# ADF4356.net
KiCad netlist of a schematic drawn in Altium Designer
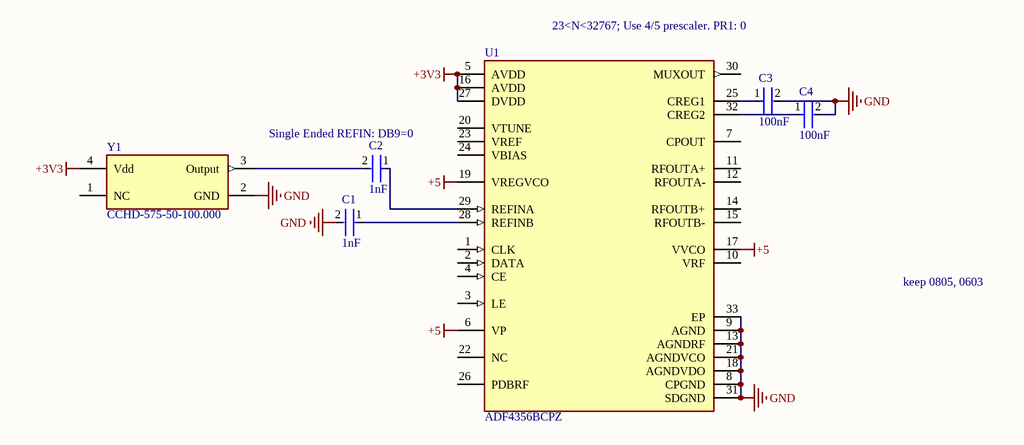
[diagram p0: ADF4356.SchDoc]

(export (version "E")
  (design (tool "Eeschema 10.0.6"))
  (components
    (comp (ref "C1")
      (value "1nF")
      (footprint "FP-C0603C-CF-MFG")
      (description "C0603 1,000 pF X7R 30ppm/°C 20.00% 50 V")
      (fields
        (field (name "MANUFACTURER PART NUMBER") "C0603C102M5RAC7411")
        (field (name "OCTOPART") "https://octopart.com/c0603c102m5rac7411-kemet-3864814")
      )
      (libsource (lib "Altium Content Vault") (part "b4654b650e69147ec39a6b967a45e02"))
    )
    (comp (ref "C2")
      (value "1nF")
      (footprint "FP-C0603C-CF-MFG")
      (description "C0603 1,000 pF X7R 30ppm/°C 20.00% 50 V")
      (fields
        (field (name "MANUFACTURER PART NUMBER") "C0603C102M5RAC7411")
        (field (name "OCTOPART") "https://octopart.com/c0603c102m5rac7411-kemet-3864814")
      )
      (libsource (lib "Altium Content Vault") (part "b4654b650e69147ec39a6b967a45e02"))
    )
    (comp (ref "C3")
      (value "100nF")
      (footprint "FP-CL21-IPC_C")
      (description "CL21 Series 0805 100nF 50V ±10% Tolerance X7R Multilayer Ceramic Chip Capacitor")
      (fields (field (name "TOLERANCE") "10%"))
      (libsource (lib "Altium Content Vault") (part "b4654b650e69147ec39a6b967a45e02"))
    )
    (comp (ref "C4")
      (value "100nF")
      (footprint "FP-CL21-IPC_C")
      (description "CL21 Series 0805 100nF 50V ±10% Tolerance X7R Multilayer Ceramic Chip Capacitor")
      (fields (field (name "TOLERANCE") "10%"))
      (libsource (lib "Altium Content Vault") (part "b4654b650e69147ec39a6b967a45e02"))
    )
    (comp (ref "U1")
      (value "ADF4356BCPZ")
      (footprint "FP-CP-32-12-IPC_B")
      (description "IC SYNTH PLL VCO 6.8GHZ 32LFCSP")
      (libsource (lib "Altium Content Vault") (part "cdbcdcc730339eae005488d77bf65b3"))
    )
    (comp (ref "Y1")
      (value "CCHD-575-50-100.000")
      (footprint "FP-CCHD-575-50-100_000-MFG")
      (description "XTAL OSC XO 100.0000MHZ HCMOS")
      (libsource (lib "Altium Content Vault") (part "8634ddfb76517a8b2207d3d7830fd32"))
    )
  )
  (nets
    (net (code "1") (name "+3V3") (class "Default")
      (node (ref "U1") (pin "16") (pinfunction "AVDD_16") (pintype "power_in"))
      (node (ref "U1") (pin "27") (pinfunction "DVDD_27") (pintype "power_in"))
      (node (ref "U1") (pin "5") (pinfunction "AVDD_5") (pintype "power_in"))
      (node (ref "Y1") (pin "4") (pinfunction "Vdd_4") (pintype "power_in"))
    )
    (net (code "2") (name "+5") (class "Default")
      (node (ref "U1") (pin "17") (pinfunction "VVCO_17") (pintype "power_in"))
      (node (ref "U1") (pin "19") (pinfunction "VREGVCO_19") (pintype "power_in"))
      (node (ref "U1") (pin "6") (pinfunction "VP_6") (pintype "passive"))
    )
    (net (code "3") (name "GND") (class "Default")
      (node (ref "C1") (pin "2") (pinfunction "2_2") (pintype "passive"))
      (node (ref "C3") (pin "2") (pinfunction "2_2") (pintype "passive"))
      (node (ref "C4") (pin "2") (pinfunction "2_2") (pintype "passive"))
      (node (ref "U1") (pin "13") (pinfunction "AGNDRF_13") (pintype "power_in"))
      (node (ref "U1") (pin "18") (pinfunction "AGNDVDO_18") (pintype "power_in"))
      (node (ref "U1") (pin "21") (pinfunction "AGNDVCO_21") (pintype "power_in"))
      (node (ref "U1") (pin "31") (pinfunction "SDGND_31") (pintype "power_in"))
      (node (ref "U1") (pin "33") (pinfunction "EP_33") (pintype "passive"))
      (node (ref "U1") (pin "8") (pinfunction "CPGND_8") (pintype "power_in"))
      (node (ref "U1") (pin "9") (pinfunction "AGND_9") (pintype "power_in"))
      (node (ref "Y1") (pin "2") (pinfunction "GND_2") (pintype "power_in"))
    )
    (net (code "4") (name "Net-(U1-CREG1)") (class "Default")
      (node (ref "C3") (pin "1") (pinfunction "1_1") (pintype "passive"))
      (node (ref "U1") (pin "25") (pinfunction "CREG1_25") (pintype "passive"))
    )
    (net (code "5") (name "Net-(U1-CREG2)") (class "Default")
      (node (ref "C4") (pin "1") (pinfunction "1_1") (pintype "passive"))
      (node (ref "U1") (pin "32") (pinfunction "CREG2_32") (pintype "passive"))
    )
    (net (code "6") (name "Net-(U1-REFINA)") (class "Default")
      (node (ref "C2") (pin "1") (pinfunction "1_1") (pintype "passive"))
      (node (ref "U1") (pin "29") (pinfunction "REFINA_29") (pintype "input"))
    )
    (net (code "7") (name "Net-(U1-REFINB)") (class "Default")
      (node (ref "C1") (pin "1") (pinfunction "1_1") (pintype "passive"))
      (node (ref "U1") (pin "28") (pinfunction "REFINB_28") (pintype "input"))
    )
    (net (code "8") (name "Net-(Y1-Output)") (class "Default")
      (node (ref "C2") (pin "2") (pinfunction "2_2") (pintype "passive"))
      (node (ref "Y1") (pin "3") (pinfunction "Output_3") (pintype "output"))
    )
    (net (code "9") (name "unconnected-(U1-CE-Pad4)") (class "Default")
      (node (ref "U1") (pin "4") (pinfunction "CE_4") (pintype "input"))
    )
    (net (code "10") (name "unconnected-(U1-CLK-Pad1)") (class "Default")
      (node (ref "U1") (pin "1") (pinfunction "CLK_1") (pintype "input"))
    )
    (net (code "11") (name "unconnected-(U1-CPOUT-Pad7)") (class "Default")
      (node (ref "U1") (pin "7") (pinfunction "CPOUT_7") (pintype "passive"))
    )
    (net (code "12") (name "unconnected-(U1-DATA-Pad2)") (class "Default")
      (node (ref "U1") (pin "2") (pinfunction "DATA_2") (pintype "input"))
    )
    (net (code "13") (name "unconnected-(U1-LE-Pad3)") (class "Default")
      (node (ref "U1") (pin "3") (pinfunction "LE_3") (pintype "input"))
    )
    (net (code "14") (name "unconnected-(U1-MUXOUT-Pad30)") (class "Default")
      (node (ref "U1") (pin "30") (pinfunction "MUXOUT_30") (pintype "output"))
    )
    (net (code "15") (name "unconnected-(U1-NC-Pad22)") (class "Default")
      (node (ref "U1") (pin "22") (pinfunction "NC_22") (pintype "passive"))
    )
    (net (code "16") (name "unconnected-(U1-PDBRF-Pad26)") (class "Default")
      (node (ref "U1") (pin "26") (pinfunction "PDBRF_26") (pintype "passive"))
    )
    (net (code "17") (name "unconnected-(U1-RFOUTA+-Pad11)") (class "Default")
      (node (ref "U1") (pin "11") (pinfunction "RFOUTA+_11") (pintype "passive"))
    )
    (net (code "18") (name "unconnected-(U1-RFOUTA--Pad12)") (class "Default")
      (node (ref "U1") (pin "12") (pinfunction "RFOUTA-_12") (pintype "passive"))
    )
    (net (code "19") (name "unconnected-(U1-RFOUTB+-Pad14)") (class "Default")
      (node (ref "U1") (pin "14") (pinfunction "RFOUTB+_14") (pintype "passive"))
    )
    (net (code "20") (name "unconnected-(U1-RFOUTB--Pad15)") (class "Default")
      (node (ref "U1") (pin "15") (pinfunction "RFOUTB-_15") (pintype "passive"))
    )
    (net (code "21") (name "unconnected-(U1-VBIAS-Pad24)") (class "Default")
      (node (ref "U1") (pin "24") (pinfunction "VBIAS_24") (pintype "passive"))
    )
    (net (code "22") (name "unconnected-(U1-VREF-Pad23)") (class "Default")
      (node (ref "U1") (pin "23") (pinfunction "VREF_23") (pintype "passive"))
    )
    (net (code "23") (name "unconnected-(U1-VRF-Pad10)") (class "Default")
      (node (ref "U1") (pin "10") (pinfunction "VRF_10") (pintype "passive"))
    )
    (net (code "24") (name "unconnected-(U1-VTUNE-Pad20)") (class "Default")
      (node (ref "U1") (pin "20") (pinfunction "VTUNE_20") (pintype "passive"))
    )
    (net (code "25") (name "unconnected-(Y1-NC-Pad1)") (class "Default")
      (node (ref "Y1") (pin "1") (pinfunction "NC_1") (pintype "passive"))
    )
  )
)
